# gatedriver_trafo_sma_compact_ACDC_3PS.net
KiCad netlist of a schematic drawn in EAGLE
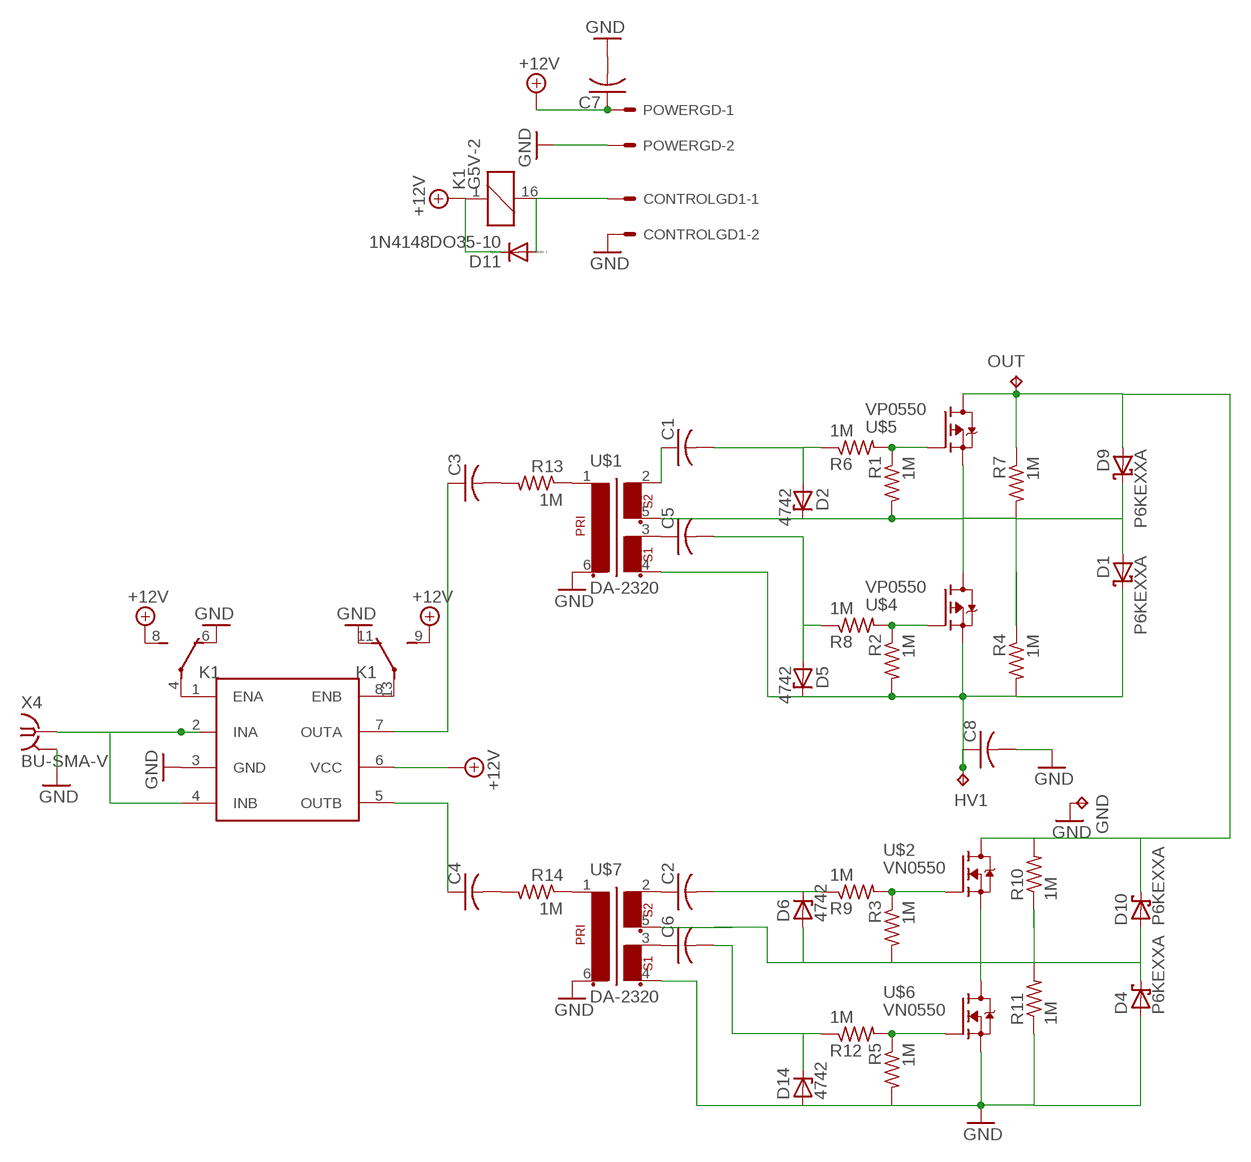
[diagram p0: schematic, sheet 1]

(export (version "E")
  (design (tool "Eeschema 10.0.6"))
  (components
    (comp (ref "C1")
      (value "C-US050-055X075")
      (footprint "eagle-import:C050-055X075")
      (libsource (lib "eagle-import") (part "resistor_C-US050-055X075"))
    )
    (comp (ref "C2")
      (value "C-US050-055X075")
      (footprint "eagle-import:C050-055X075")
      (libsource (lib "eagle-import") (part "resistor_C-US050-055X075"))
    )
    (comp (ref "C3")
      (value "C-US050-055X075")
      (footprint "eagle-import:C050-055X075")
      (libsource (lib "eagle-import") (part "resistor_C-US050-055X075"))
    )
    (comp (ref "C4")
      (value "C-US050-055X075")
      (footprint "eagle-import:C050-055X075")
      (libsource (lib "eagle-import") (part "resistor_C-US050-055X075"))
    )
    (comp (ref "C5")
      (value "C-US050-055X075")
      (footprint "eagle-import:C050-055X075")
      (libsource (lib "eagle-import") (part "resistor_C-US050-055X075"))
    )
    (comp (ref "C6")
      (value "C-US050-055X075")
      (footprint "eagle-import:C050-055X075")
      (libsource (lib "eagle-import") (part "resistor_C-US050-055X075"))
    )
    (comp (ref "C7")
      (value "C-US050-030X075")
      (footprint "eagle-import:C050-030X075")
      (libsource (lib "eagle-import") (part "C-US050-030X075"))
    )
    (comp (ref "C8")
      (value "C-US102-064X133")
      (footprint "eagle-import:C102-064X133")
      (libsource (lib "eagle-import") (part "resistor_C-US102-064X133"))
    )
    (comp (ref "CONTROLGD1")
      (value "KK-156-2")
      (footprint "eagle-import:KK-156-2")
      (libsource (lib "eagle-import") (part "KK-156-2"))
    )
    (comp (ref "D1")
      (value "P6KEXXA")
      (footprint "eagle-import:C1702-15")
      (libsource (lib "eagle-import") (part "P6KEXXA"))
    )
    (comp (ref "D2")
      (value "4742")
      (footprint "eagle-import:ZDIO-10")
      (libsource (lib "eagle-import") (part "ZENER-DIODEZD-10"))
    )
    (comp (ref "D4")
      (value "P6KEXXA")
      (footprint "eagle-import:C1702-15")
      (libsource (lib "eagle-import") (part "P6KEXXA"))
    )
    (comp (ref "D5")
      (value "4742")
      (footprint "eagle-import:ZDIO-10")
      (libsource (lib "eagle-import") (part "ZENER-DIODEZD-10"))
    )
    (comp (ref "D6")
      (value "4742")
      (footprint "eagle-import:ZDIO-10")
      (libsource (lib "eagle-import") (part "ZENER-DIODEZD-10"))
    )
    (comp (ref "D9")
      (value "P6KEXXA")
      (footprint "eagle-import:C1702-15")
      (libsource (lib "eagle-import") (part "P6KEXXA"))
    )
    (comp (ref "D10")
      (value "P6KEXXA")
      (footprint "eagle-import:C1702-15")
      (libsource (lib "eagle-import") (part "P6KEXXA"))
    )
    (comp (ref "D11")
      (value "1N4148DO35-10")
      (footprint "eagle-import:DO35-10")
      (libsource (lib "eagle-import") (part "1N4148DO35-10"))
    )
    (comp (ref "D14")
      (value "4742")
      (footprint "eagle-import:ZDIO-10")
      (libsource (lib "eagle-import") (part "ZENER-DIODEZD-10"))
    )
    (comp (ref "GND")
      (value "TPPAD1-20Y")
      (footprint "eagle-import:P1-20Y")
      (libsource (lib "eagle-import") (part "TPPAD1-20Y"))
    )
    (comp (ref "HV1")
      (value "TPPAD1-20Y")
      (footprint "eagle-import:P1-20Y")
      (libsource (lib "eagle-import") (part "TPPAD1-20Y"))
    )
    (comp (ref "K1")
      (value "G5V-2")
      (footprint "eagle-import:G5V-2")
      (fields (field (name "MPN") "G5V-2 5DC"))
      (libsource (lib "eagle-import") (part "G5V-2"))
    )
    (comp (ref "OUT")
      (value "TPPAD1-20Y")
      (footprint "eagle-import:P1-20Y")
      (libsource (lib "eagle-import") (part "TPPAD1-20Y"))
    )
    (comp (ref "POWERGD")
      (value "KK-156-2")
      (footprint "eagle-import:KK-156-2")
      (libsource (lib "eagle-import") (part "KK-156-2"))
    )
    (comp (ref "R1")
      (value "1M")
      (footprint "eagle-import:0207_10")
      (libsource (lib "eagle-import") (part "R-US_0207/10"))
    )
    (comp (ref "R2")
      (value "1M")
      (footprint "eagle-import:0207_10")
      (libsource (lib "eagle-import") (part "R-US_0207/10"))
    )
    (comp (ref "R3")
      (value "1M")
      (footprint "eagle-import:0207_10")
      (libsource (lib "eagle-import") (part "R-US_0207/10"))
    )
    (comp (ref "R4")
      (value "1M")
      (footprint "eagle-import:0207_10")
      (libsource (lib "eagle-import") (part "R-US_0207/10"))
    )
    (comp (ref "R5")
      (value "1M")
      (footprint "eagle-import:0207_10")
      (libsource (lib "eagle-import") (part "R-US_0207/10"))
    )
    (comp (ref "R6")
      (value "1M")
      (footprint "eagle-import:0207_10")
      (libsource (lib "eagle-import") (part "R-US_0207/10"))
    )
    (comp (ref "R7")
      (value "1M")
      (footprint "eagle-import:0207_10")
      (libsource (lib "eagle-import") (part "R-US_0207/10"))
    )
    (comp (ref "R8")
      (value "1M")
      (footprint "eagle-import:0207_10")
      (libsource (lib "eagle-import") (part "R-US_0207/10"))
    )
    (comp (ref "R9")
      (value "1M")
      (footprint "eagle-import:0207_10")
      (libsource (lib "eagle-import") (part "R-US_0207/10"))
    )
    (comp (ref "R10")
      (value "1M")
      (footprint "eagle-import:0207_10")
      (libsource (lib "eagle-import") (part "R-US_0207/10"))
    )
    (comp (ref "R11")
      (value "1M")
      (footprint "eagle-import:0207_10")
      (libsource (lib "eagle-import") (part "R-US_0207/10"))
    )
    (comp (ref "R12")
      (value "1M")
      (footprint "eagle-import:0207_10")
      (libsource (lib "eagle-import") (part "R-US_0207/10"))
    )
    (comp (ref "R13")
      (value "1M")
      (footprint "eagle-import:0207_12")
      (libsource (lib "eagle-import") (part "R-US_0207/12"))
    )
    (comp (ref "R14")
      (value "1M")
      (footprint "eagle-import:0207_12")
      (libsource (lib "eagle-import") (part "R-US_0207/12"))
    )
    (comp (ref "U$1")
      (value "DA-2320")
      (footprint "eagle-import:DIL06")
      (libsource (lib "eagle-import") (part "DA-2320"))
    )
    (comp (ref "U$2")
      (value "VN0550")
      (footprint "eagle-import:TO92-")
      (libsource (lib "eagle-import") (part "VN0550"))
    )
    (comp (ref "U$3")
      (value "UCC27425")
      (footprint "eagle-import:DIL08")
      (libsource (lib "eagle-import") (part "UCC27425"))
    )
    (comp (ref "U$4")
      (value "VP0550")
      (footprint "eagle-import:TO92-")
      (libsource (lib "eagle-import") (part "VP0550"))
    )
    (comp (ref "U$5")
      (value "VP0550")
      (footprint "eagle-import:TO92-")
      (libsource (lib "eagle-import") (part "VP0550"))
    )
    (comp (ref "U$6")
      (value "VN0550")
      (footprint "eagle-import:TO92-")
      (libsource (lib "eagle-import") (part "VN0550"))
    )
    (comp (ref "U$7")
      (value "DA-2320")
      (footprint "eagle-import:DIL06")
      (libsource (lib "eagle-import") (part "DA-2320"))
    )
    (comp (ref "X4")
      (value "BU-SMA-V")
      (footprint "eagle-import:BU-SMA-V")
      (libsource (lib "eagle-import") (part "BU-SMA-V"))
    )
  )
  (nets
    (net (code "1") (name "+12V") (class "Default")
      (node (ref "C7") (pin "1") (pinfunction "1_1") (pintype "passive"))
      (node (ref "D11") (pin "C") (pinfunction "C_C") (pintype "passive"))
      (node (ref "K1") (pin "1") (pinfunction "1_1") (pintype "passive"))
      (node (ref "K1") (pin "8") (pinfunction "S_8") (pintype "passive"))
      (node (ref "K1") (pin "9") (pinfunction "S_9") (pintype "passive"))
      (node (ref "POWERGD") (pin "1") (pinfunction "S_1") (pintype "passive"))
      (node (ref "U$3") (pin "6") (pinfunction "VCC_6") (pintype "bidirectional"))
    )
    (net (code "2") (name "/N$25") (class "Default")
      (node (ref "C2") (pin "2") (pinfunction "2_2") (pintype "passive"))
      (node (ref "D6") (pin "C") (pinfunction "C_C") (pintype "passive"))
      (node (ref "R3") (pin "1") (pinfunction "1_1") (pintype "passive"))
      (node (ref "R9") (pin "1") (pinfunction "1_1") (pintype "passive"))
      (node (ref "R9") (pin "2") (pinfunction "2_2") (pintype "passive"))
      (node (ref "U$2") (pin "2") (pinfunction "G_2") (pintype "passive"))
    )
    (net (code "3") (name "GND") (class "Default")
      (node (ref "C7") (pin "2") (pinfunction "2_2") (pintype "passive"))
      (node (ref "C8") (pin "2") (pinfunction "2_2") (pintype "passive"))
      (node (ref "CONTROLGD1") (pin "2") (pinfunction "S_2") (pintype "passive"))
      (node (ref "D14") (pin "A") (pinfunction "A_A") (pintype "passive"))
      (node (ref "D4") (pin "A") (pinfunction "A_A") (pintype "passive"))
      (node (ref "GND") (pin "TP") (pinfunction "TP_TP") (pintype "input"))
      (node (ref "K1") (pin "11") (pinfunction "O_11") (pintype "passive"))
      (node (ref "K1") (pin "6") (pinfunction "O_6") (pintype "passive"))
      (node (ref "POWERGD") (pin "2") (pinfunction "S_2") (pintype "passive"))
      (node (ref "R11") (pin "1") (pinfunction "1_1") (pintype "passive"))
      (node (ref "U$1") (pin "6") (pinfunction "2_6") (pintype "passive"))
      (node (ref "U$3") (pin "3") (pinfunction "GND_3") (pintype "bidirectional"))
      (node (ref "U$6") (pin "3") (pinfunction "S_3") (pintype "passive"))
      (node (ref "U$7") (pin "4") (pinfunction "3_4") (pintype "passive"))
      (node (ref "U$7") (pin "6") (pinfunction "2_6") (pintype "passive"))
      (node (ref "X4") (pin "2") (pinfunction "2_2") (pintype "passive"))
      (node (ref "X4") (pin "3") (pinfunction "2_3") (pintype "passive"))
      (node (ref "X4") (pin "4") (pinfunction "2_4") (pintype "passive"))
      (node (ref "X4") (pin "5") (pinfunction "2_5") (pintype "passive"))
    )
    (net (code "4") (name "Net-(C1-Pad2)") (class "Default")
      (node (ref "C1") (pin "2") (pinfunction "2_2") (pintype "passive"))
      (node (ref "D2") (pin "A") (pinfunction "A_A") (pintype "passive"))
      (node (ref "R6") (pin "1") (pinfunction "1_1") (pintype "passive"))
    )
    (net (code "5") (name "Net-(C3-Pad2)") (class "Default")
      (node (ref "C3") (pin "2") (pinfunction "2_2") (pintype "passive"))
      (node (ref "R13") (pin "2") (pinfunction "2_2") (pintype "passive"))
    )
    (net (code "6") (name "Net-(C4-Pad2)") (class "Default")
      (node (ref "C4") (pin "2") (pinfunction "2_2") (pintype "passive"))
      (node (ref "R14") (pin "2") (pinfunction "2_2") (pintype "passive"))
    )
    (net (code "7") (name "Net-(C5-Pad2)") (class "Default")
      (node (ref "C5") (pin "2") (pinfunction "2_2") (pintype "passive"))
      (node (ref "D5") (pin "A") (pinfunction "A_A") (pintype "passive"))
      (node (ref "R8") (pin "1") (pinfunction "1_1") (pintype "passive"))
    )
    (net (code "8") (name "Net-(C6-Pad2)") (class "Default")
      (node (ref "C6") (pin "2") (pinfunction "2_2") (pintype "passive"))
      (node (ref "D14") (pin "C") (pinfunction "C_C") (pintype "passive"))
      (node (ref "R12") (pin "1") (pinfunction "1_1") (pintype "passive"))
    )
    (net (code "9") (name "Net-(CONTROLGD1A-S)") (class "Default")
      (node (ref "CONTROLGD1") (pin "1") (pinfunction "S_1") (pintype "passive"))
      (node (ref "D11") (pin "A") (pinfunction "A_A") (pintype "passive"))
      (node (ref "K1") (pin "16") (pinfunction "2_16") (pintype "passive"))
    )
    (net (code "10") (name "Net-(K1A-P)") (class "Default")
      (node (ref "K1") (pin "4") (pinfunction "P_4") (pintype "passive"))
      (node (ref "U$3") (pin "1") (pinfunction "ENA_1") (pintype "bidirectional"))
    )
    (net (code "11") (name "Net-(K1B-P)") (class "Default")
      (node (ref "K1") (pin "13") (pinfunction "P_13") (pintype "passive"))
      (node (ref "U$3") (pin "8") (pinfunction "ENB_8") (pintype "bidirectional"))
    )
    (net (code "12") (name "Net-(R13-Pad1)") (class "Default")
      (node (ref "R13") (pin "1") (pinfunction "1_1") (pintype "passive"))
      (node (ref "U$1") (pin "1") (pinfunction "1_1") (pintype "passive"))
    )
    (net (code "13") (name "Net-(R14-Pad1)") (class "Default")
      (node (ref "R14") (pin "1") (pinfunction "1_1") (pintype "passive"))
      (node (ref "U$7") (pin "1") (pinfunction "1_1") (pintype "passive"))
    )
    (net (code "14") (name "Net-(U$1-3)") (class "Default")
      (node (ref "C8") (pin "1") (pinfunction "1_1") (pintype "passive"))
      (node (ref "D1") (pin "C") (pinfunction "C_C") (pintype "passive"))
      (node (ref "D5") (pin "C") (pinfunction "C_C") (pintype "passive"))
      (node (ref "HV1") (pin "TP") (pinfunction "TP_TP") (pintype "input"))
      (node (ref "R2") (pin "2") (pinfunction "2_2") (pintype "passive"))
      (node (ref "R4") (pin "2") (pinfunction "2_2") (pintype "passive"))
      (node (ref "U$1") (pin "4") (pinfunction "3_4") (pintype "passive"))
      (node (ref "U$4") (pin "3") (pinfunction "S_3") (pintype "passive"))
    )
    (net (code "15") (name "Net-(U$1-4)") (class "Default")
      (node (ref "C5") (pin "1") (pinfunction "1_1") (pintype "passive"))
      (node (ref "U$1") (pin "3") (pinfunction "4_3") (pintype "passive"))
    )
    (net (code "16") (name "Net-(U$1-6)") (class "Default")
      (node (ref "C1") (pin "1") (pinfunction "1_1") (pintype "passive"))
      (node (ref "U$1") (pin "2") (pinfunction "6_2") (pintype "passive"))
    )
    (net (code "17") (name "Net-(U$2-D)") (class "Default")
      (node (ref "D10") (pin "C") (pinfunction "C_C") (pintype "passive"))
      (node (ref "D9") (pin "A") (pinfunction "A_A") (pintype "passive"))
      (node (ref "OUT") (pin "TP") (pinfunction "TP_TP") (pintype "input"))
      (node (ref "R10") (pin "2") (pinfunction "2_2") (pintype "passive"))
      (node (ref "R7") (pin "1") (pinfunction "1_1") (pintype "passive"))
      (node (ref "U$2") (pin "1") (pinfunction "D_1") (pintype "passive"))
      (node (ref "U$5") (pin "1") (pinfunction "D_1") (pintype "passive"))
    )
    (net (code "18") (name "Net-(U$2-S)") (class "Default")
      (node (ref "D10") (pin "A") (pinfunction "A_A") (pintype "passive"))
      (node (ref "D4") (pin "C") (pinfunction "C_C") (pintype "passive"))
      (node (ref "D6") (pin "A") (pinfunction "A_A") (pintype "passive"))
      (node (ref "R10") (pin "1") (pinfunction "1_1") (pintype "passive"))
      (node (ref "R11") (pin "2") (pinfunction "2_2") (pintype "passive"))
      (node (ref "U$2") (pin "3") (pinfunction "S_3") (pintype "passive"))
      (node (ref "U$6") (pin "1") (pinfunction "D_1") (pintype "passive"))
    )
    (net (code "19") (name "Net-(U$3-INA)") (class "Default")
      (node (ref "U$3") (pin "2") (pinfunction "INA_2") (pintype "bidirectional"))
      (node (ref "U$3") (pin "4") (pinfunction "INB_4") (pintype "bidirectional"))
      (node (ref "X4") (pin "1") (pinfunction "1_1") (pintype "passive"))
    )
    (net (code "20") (name "Net-(U$3-OUTA)") (class "Default")
      (node (ref "C3") (pin "1") (pinfunction "1_1") (pintype "passive"))
      (node (ref "U$3") (pin "7") (pinfunction "OUTA_7") (pintype "bidirectional"))
    )
    (net (code "21") (name "Net-(U$3-OUTB)") (class "Default")
      (node (ref "C4") (pin "1") (pinfunction "1_1") (pintype "passive"))
      (node (ref "U$3") (pin "5") (pinfunction "OUTB_5") (pintype "bidirectional"))
    )
    (net (code "22") (name "Net-(U$4-D)") (class "Default")
      (node (ref "D1") (pin "A") (pinfunction "A_A") (pintype "passive"))
      (node (ref "D2") (pin "C") (pinfunction "C_C") (pintype "passive"))
      (node (ref "D9") (pin "C") (pinfunction "C_C") (pintype "passive"))
      (node (ref "R1") (pin "2") (pinfunction "2_2") (pintype "passive"))
      (node (ref "R4") (pin "1") (pinfunction "1_1") (pintype "passive"))
      (node (ref "R7") (pin "2") (pinfunction "2_2") (pintype "passive"))
      (node (ref "U$1") (pin "5") (pinfunction "5_5") (pintype "passive"))
      (node (ref "U$4") (pin "1") (pinfunction "D_1") (pintype "passive"))
      (node (ref "U$5") (pin "3") (pinfunction "S_3") (pintype "passive"))
    )
    (net (code "23") (name "Net-(U$4-G)") (class "Default")
      (node (ref "R2") (pin "1") (pinfunction "1_1") (pintype "passive"))
      (node (ref "R8") (pin "2") (pinfunction "2_2") (pintype "passive"))
      (node (ref "U$4") (pin "2") (pinfunction "G_2") (pintype "passive"))
    )
    (net (code "24") (name "Net-(U$5-G)") (class "Default")
      (node (ref "R1") (pin "1") (pinfunction "1_1") (pintype "passive"))
      (node (ref "R6") (pin "2") (pinfunction "2_2") (pintype "passive"))
      (node (ref "U$5") (pin "2") (pinfunction "G_2") (pintype "passive"))
    )
    (net (code "25") (name "Net-(U$6-G)") (class "Default")
      (node (ref "R12") (pin "2") (pinfunction "2_2") (pintype "passive"))
      (node (ref "R5") (pin "1") (pinfunction "1_1") (pintype "passive"))
      (node (ref "U$6") (pin "2") (pinfunction "G_2") (pintype "passive"))
    )
    (net (code "26") (name "Net-(U$7-4)") (class "Default")
      (node (ref "C6") (pin "1") (pinfunction "1_1") (pintype "passive"))
      (node (ref "U$7") (pin "3") (pinfunction "4_3") (pintype "passive"))
    )
    (net (code "27") (name "Net-(U$7-6)") (class "Default")
      (node (ref "C2") (pin "1") (pinfunction "1_1") (pintype "passive"))
      (node (ref "U$7") (pin "2") (pinfunction "6_2") (pintype "passive"))
    )
    (net (code "28") (name "unconnected-(R3-Pad2)") (class "Default")
      (node (ref "R3") (pin "2") (pinfunction "2_2") (pintype "passive"))
    )
    (net (code "29") (name "unconnected-(R5-Pad2)") (class "Default")
      (node (ref "R5") (pin "2") (pinfunction "2_2") (pintype "passive"))
    )
    (net (code "30") (name "unconnected-(U$7-Pad5)") (class "Default")
      (node (ref "U$7") (pin "5") (pinfunction "5_5") (pintype "passive"))
    )
  )
)
